# ProPrj_C64_Printer_Interface_2025-09-17.net
KiCad netlist of a schematic drawn in EasyEDA Pro
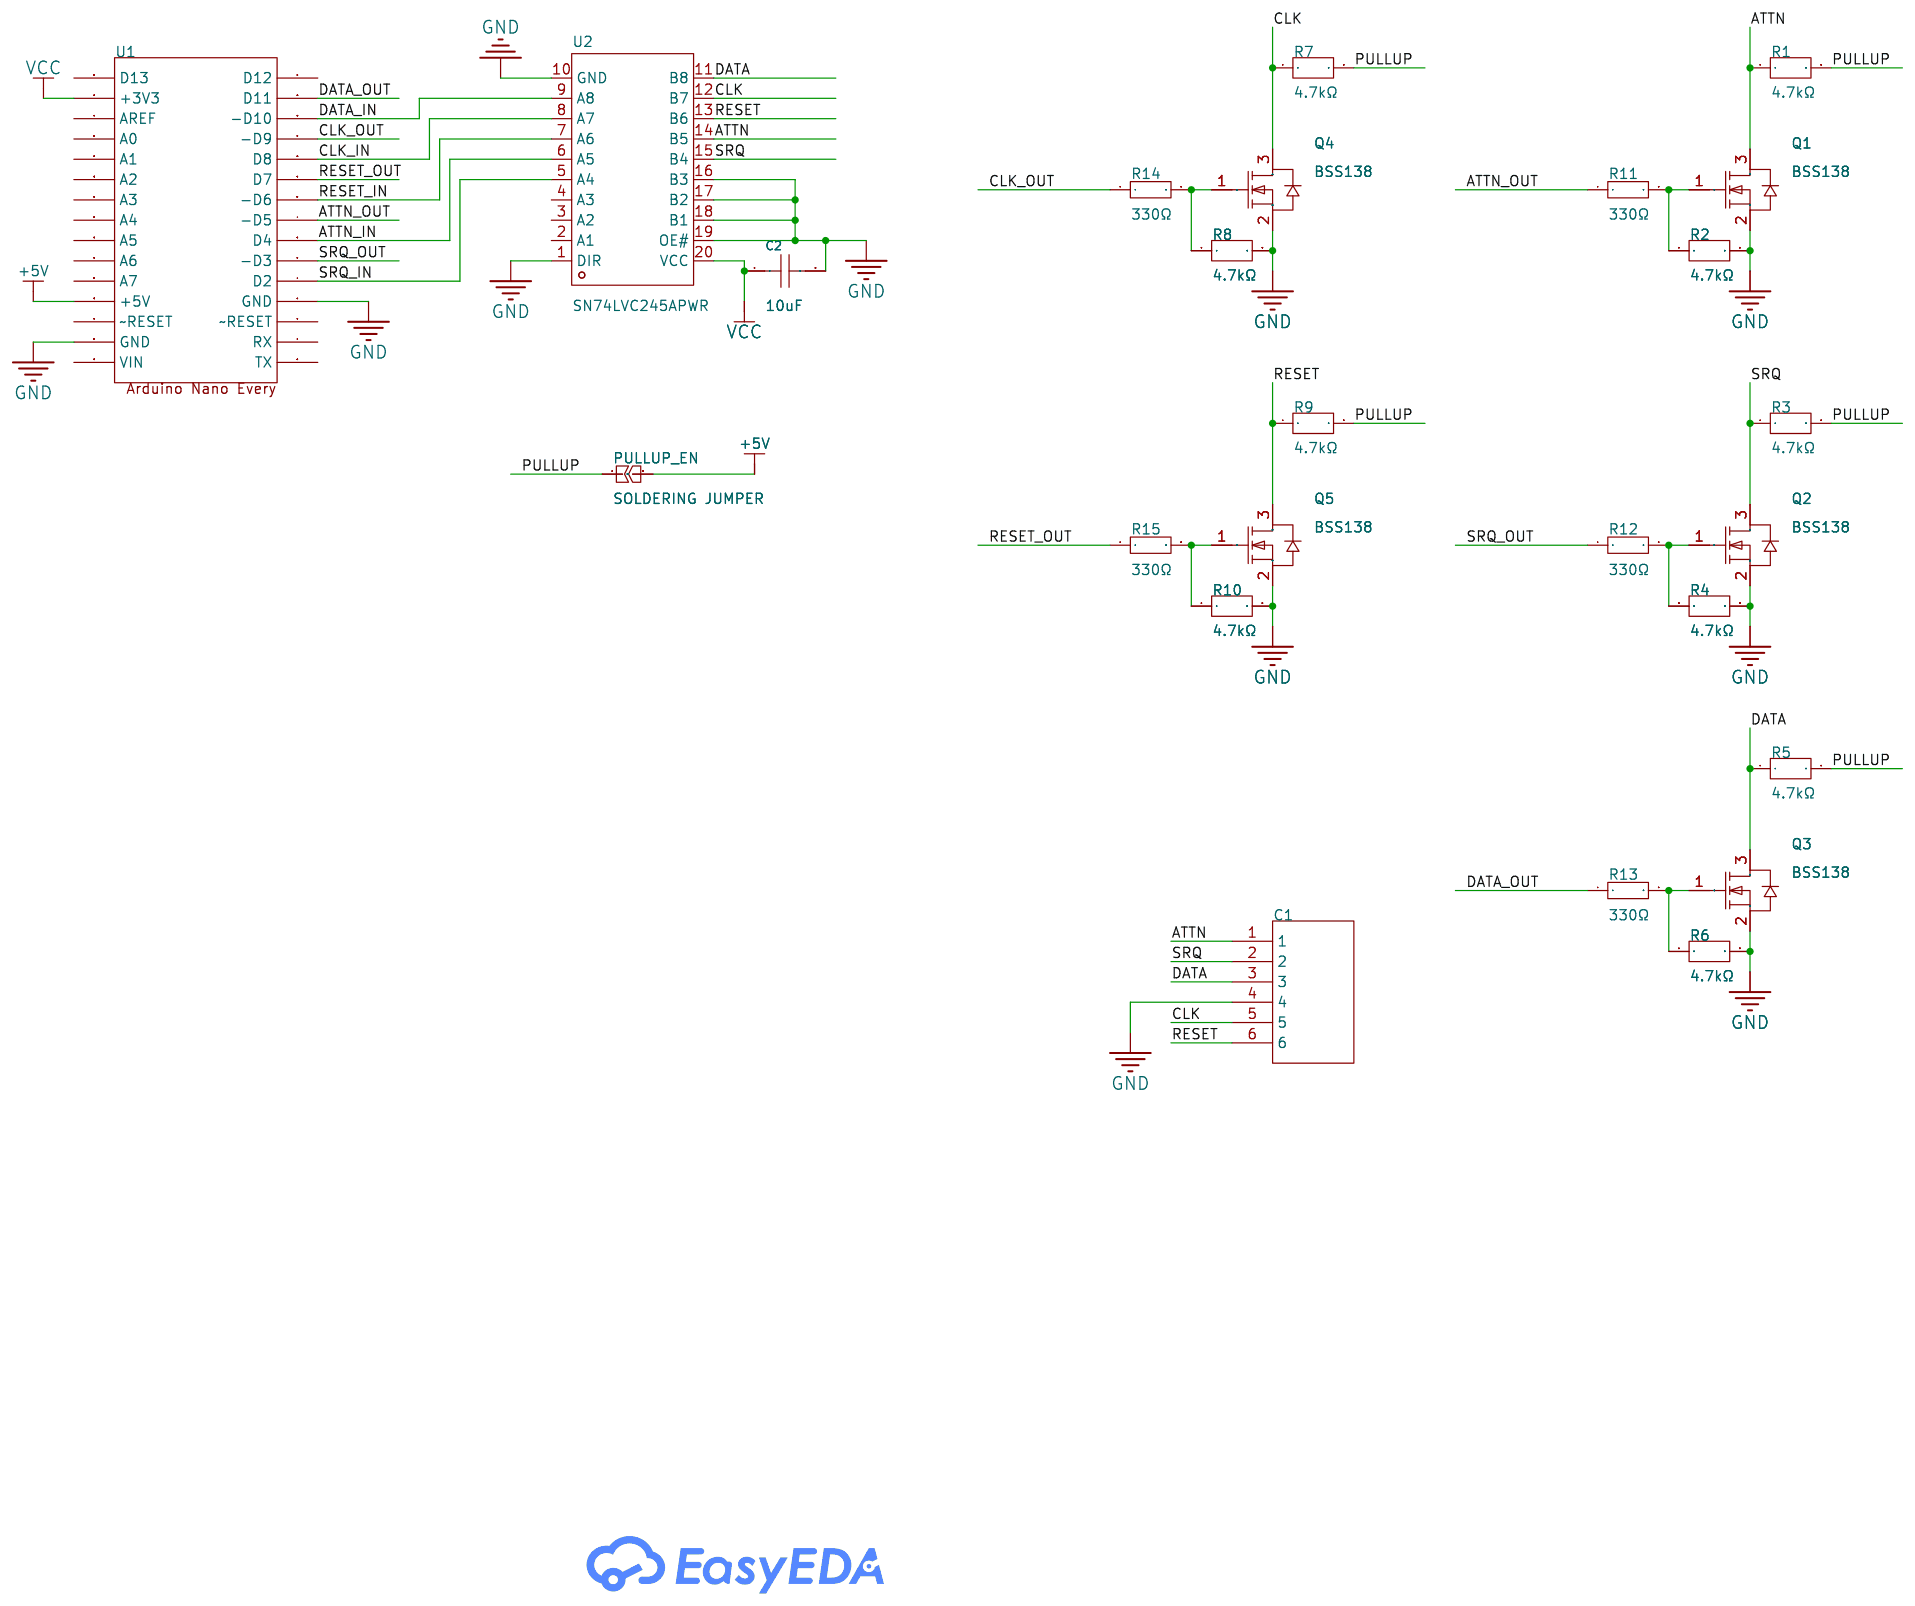
[diagram p0: schematic sheet]

(export (version "E")
  (design (tool "Eeschema 10.0.6"))
  (components
    (comp (ref "C1")
      (value "DIN 6")
      (footprint "easyedapro:FC680806")
      (libsource (lib "easyedapro") (part "FC680806 DIN 6 240°"))
    )
    (comp (ref "C2")
      (value "10uF")
      (footprint "easyedapro:C0603")
      (description "Capacitance:10uF Tolerance:±20% Tolerance:±20% Voltage Rating:25V Temperature Coefficient:X5R")
      (fields
        (field (name "Manufacturer Part") "CL10A106MA8NRNC")
        (field (name "Manufacturer") "SAMSUNG(三星)")
      )
      (libsource (lib "easyedapro") (part "CL10A106MA8NRNC"))
    )
    (comp (ref "PULLUP_EN")
      (value "SOLDERING JUMPER")
      (footprint "easyedapro:JUMPER")
      (libsource (lib "easyedapro") (part "Jumper 3pin"))
    )
    (comp (ref "Q1")
      (value "BSS138")
      (footprint "easyedapro:SOT-23_L2.9-W1.3-P1.90-LS2.4-BR")
      (fields (field (name "Manufacturer") "GOODWORK(固得沃克)"))
      (libsource (lib "easyedapro") (part "BSS138_C2938375"))
    )
    (comp (ref "Q2")
      (value "BSS138")
      (footprint "easyedapro:SOT-23_L2.9-W1.3-P1.90-LS2.4-BR")
      (fields (field (name "Manufacturer") "GOODWORK(固得沃克)"))
      (libsource (lib "easyedapro") (part "BSS138_C2938375"))
    )
    (comp (ref "Q3")
      (value "BSS138")
      (footprint "easyedapro:SOT-23_L2.9-W1.3-P1.90-LS2.4-BR")
      (fields (field (name "Manufacturer") "GOODWORK(固得沃克)"))
      (libsource (lib "easyedapro") (part "BSS138_C2938375"))
    )
    (comp (ref "Q4")
      (value "BSS138")
      (footprint "easyedapro:SOT-23_L2.9-W1.3-P1.90-LS2.4-BR")
      (fields (field (name "Manufacturer") "GOODWORK(固得沃克)"))
      (libsource (lib "easyedapro") (part "BSS138_C2938375"))
    )
    (comp (ref "Q5")
      (value "BSS138")
      (footprint "easyedapro:SOT-23_L2.9-W1.3-P1.90-LS2.4-BR")
      (fields (field (name "Manufacturer") "GOODWORK(固得沃克)"))
      (libsource (lib "easyedapro") (part "BSS138_C2938375"))
    )
    (comp (ref "R1")
      (value "4.7kΩ")
      (footprint "easyedapro:R0805")
      (fields (field (name "Manufacturer Part") "ERJ6RBD4701V") (field (name "Manufacturer") "PANASONIC(松下)"))
      (libsource (lib "easyedapro") (part "ERJ6RBD4701V"))
    )
    (comp (ref "R2")
      (value "4.7kΩ")
      (footprint "easyedapro:R0805")
      (fields (field (name "Manufacturer Part") "ERJ6RBD4701V") (field (name "Manufacturer") "PANASONIC(松下)"))
      (libsource (lib "easyedapro") (part "ERJ6RBD4701V"))
    )
    (comp (ref "R3")
      (value "4.7kΩ")
      (footprint "easyedapro:R0805")
      (fields (field (name "Manufacturer Part") "ERJ6RBD4701V") (field (name "Manufacturer") "PANASONIC(松下)"))
      (libsource (lib "easyedapro") (part "ERJ6RBD4701V"))
    )
    (comp (ref "R4")
      (value "4.7kΩ")
      (footprint "easyedapro:R0805")
      (fields (field (name "Manufacturer Part") "ERJ6RBD4701V") (field (name "Manufacturer") "PANASONIC(松下)"))
      (libsource (lib "easyedapro") (part "ERJ6RBD4701V"))
    )
    (comp (ref "R5")
      (value "4.7kΩ")
      (footprint "easyedapro:R0805")
      (fields (field (name "Manufacturer Part") "ERJ6RBD4701V") (field (name "Manufacturer") "PANASONIC(松下)"))
      (libsource (lib "easyedapro") (part "ERJ6RBD4701V"))
    )
    (comp (ref "R6")
      (value "4.7kΩ")
      (footprint "easyedapro:R0805")
      (fields (field (name "Manufacturer Part") "ERJ6RBD4701V") (field (name "Manufacturer") "PANASONIC(松下)"))
      (libsource (lib "easyedapro") (part "ERJ6RBD4701V"))
    )
    (comp (ref "R7")
      (value "4.7kΩ")
      (footprint "easyedapro:R0805")
      (fields (field (name "Manufacturer Part") "ERJ6RBD4701V") (field (name "Manufacturer") "PANASONIC(松下)"))
      (libsource (lib "easyedapro") (part "ERJ6RBD4701V"))
    )
    (comp (ref "R8")
      (value "4.7kΩ")
      (footprint "easyedapro:R0805")
      (fields (field (name "Manufacturer Part") "ERJ6RBD4701V") (field (name "Manufacturer") "PANASONIC(松下)"))
      (libsource (lib "easyedapro") (part "ERJ6RBD4701V"))
    )
    (comp (ref "R9")
      (value "4.7kΩ")
      (footprint "easyedapro:R0805")
      (fields (field (name "Manufacturer Part") "ERJ6RBD4701V") (field (name "Manufacturer") "PANASONIC(松下)"))
      (libsource (lib "easyedapro") (part "ERJ6RBD4701V"))
    )
    (comp (ref "R10")
      (value "4.7kΩ")
      (footprint "easyedapro:R0805")
      (fields (field (name "Manufacturer Part") "ERJ6RBD4701V") (field (name "Manufacturer") "PANASONIC(松下)"))
      (libsource (lib "easyedapro") (part "ERJ6RBD4701V"))
    )
    (comp (ref "R11")
      (value "330Ω")
      (footprint "easyedapro:R0603")
      (fields
        (field (name "Manufacturer Part") "0603WAF3300T5E")
        (field (name "Manufacturer") "UNI-ROYAL(厚声)")
      )
      (libsource (lib "easyedapro") (part "0603WAF3300T5E"))
    )
    (comp (ref "R12")
      (value "330Ω")
      (footprint "easyedapro:R0603")
      (fields
        (field (name "Manufacturer Part") "0603WAF3300T5E")
        (field (name "Manufacturer") "UNI-ROYAL(厚声)")
      )
      (libsource (lib "easyedapro") (part "0603WAF3300T5E"))
    )
    (comp (ref "R13")
      (value "330Ω")
      (footprint "easyedapro:R0603")
      (fields
        (field (name "Manufacturer Part") "0603WAF3300T5E")
        (field (name "Manufacturer") "UNI-ROYAL(厚声)")
      )
      (libsource (lib "easyedapro") (part "0603WAF3300T5E"))
    )
    (comp (ref "R14")
      (value "330Ω")
      (footprint "easyedapro:R0603")
      (fields
        (field (name "Manufacturer Part") "0603WAF3300T5E")
        (field (name "Manufacturer") "UNI-ROYAL(厚声)")
      )
      (libsource (lib "easyedapro") (part "0603WAF3300T5E"))
    )
    (comp (ref "R15")
      (value "330Ω")
      (footprint "easyedapro:R0603")
      (fields
        (field (name "Manufacturer Part") "0603WAF3300T5E")
        (field (name "Manufacturer") "UNI-ROYAL(厚声)")
      )
      (libsource (lib "easyedapro") (part "0603WAF3300T5E"))
    )
    (comp (ref "U1")
      (value "~")
      (footprint "easyedapro:Arduino Nano Every (SMD)")
      (libsource (lib "easyedapro") (part "Arduino Nano Every"))
    )
    (comp (ref "U2")
      (value "SN74LVC245APWR")
      (footprint "easyedapro:TSSOP-20_L6.5-W4.4-P0.65-LS6.4-BL")
      (fields (field (name "Manufacturer") "TI(德州仪器)"))
      (libsource (lib "easyedapro") (part "SN74LVC245APWR"))
    )
  )
  (nets
    (net (code "1") (name "+5V") (class "Default")
      (node (ref "PULLUP_EN") (pin "2") (pinfunction "2_2") (pintype "input"))
      (node (ref "U1") (pin "26") (pinfunction "+5V_26") (pintype "input"))
    )
    (net (code "2") (name "/ATTN") (class "Default")
      (node (ref "C1") (pin "1") (pinfunction "1_1") (pintype "input"))
      (node (ref "Q1") (pin "3") (pinfunction "D_3") (pintype "unspecified"))
      (node (ref "R1") (pin "1") (pinfunction "1_1") (pintype "unspecified"))
      (node (ref "U2") (pin "14") (pinfunction "B5_14") (pintype "unspecified"))
    )
    (net (code "3") (name "/ATTN_IN") (class "Default")
      (node (ref "U1") (pin "6") (pinfunction "D4_6") (pintype "input"))
      (node (ref "U2") (pin "6") (pinfunction "A5_6") (pintype "unspecified"))
    )
    (net (code "4") (name "/ATTN_OUT") (class "Default")
      (node (ref "R11") (pin "1") (pinfunction "1_1") (pintype "input"))
      (node (ref "U1") (pin "7") (pinfunction "-D5_7") (pintype "input"))
    )
    (net (code "5") (name "/CLK") (class "Default")
      (node (ref "C1") (pin "5") (pinfunction "5_5") (pintype "input"))
      (node (ref "Q4") (pin "3") (pinfunction "D_3") (pintype "unspecified"))
      (node (ref "R7") (pin "1") (pinfunction "1_1") (pintype "unspecified"))
      (node (ref "U2") (pin "12") (pinfunction "B7_12") (pintype "unspecified"))
    )
    (net (code "6") (name "/CLK_IN") (class "Default")
      (node (ref "U1") (pin "10") (pinfunction "D8_10") (pintype "input"))
      (node (ref "U2") (pin "8") (pinfunction "A7_8") (pintype "unspecified"))
    )
    (net (code "7") (name "/CLK_OUT") (class "Default")
      (node (ref "R14") (pin "1") (pinfunction "1_1") (pintype "input"))
      (node (ref "U1") (pin "11") (pinfunction "-D9_11") (pintype "input"))
    )
    (net (code "8") (name "/DATA") (class "Default")
      (node (ref "C1") (pin "3") (pinfunction "3_3") (pintype "input"))
      (node (ref "Q3") (pin "3") (pinfunction "D_3") (pintype "unspecified"))
      (node (ref "R5") (pin "1") (pinfunction "1_1") (pintype "unspecified"))
      (node (ref "U2") (pin "11") (pinfunction "B8_11") (pintype "unspecified"))
    )
    (net (code "9") (name "/DATA_IN") (class "Default")
      (node (ref "U1") (pin "12") (pinfunction "-D10_12") (pintype "input"))
      (node (ref "U2") (pin "9") (pinfunction "A8_9") (pintype "unspecified"))
    )
    (net (code "10") (name "/DATA_OUT") (class "Default")
      (node (ref "R13") (pin "1") (pinfunction "1_1") (pintype "input"))
      (node (ref "U1") (pin "13") (pinfunction "D11_13") (pintype "input"))
    )
    (net (code "11") (name "/PULLUP") (class "Default")
      (node (ref "PULLUP_EN") (pin "1") (pinfunction "1_1") (pintype "input"))
      (node (ref "R1") (pin "2") (pinfunction "2_2") (pintype "unspecified"))
      (node (ref "R3") (pin "2") (pinfunction "2_2") (pintype "unspecified"))
      (node (ref "R5") (pin "2") (pinfunction "2_2") (pintype "unspecified"))
      (node (ref "R7") (pin "2") (pinfunction "2_2") (pintype "unspecified"))
      (node (ref "R9") (pin "2") (pinfunction "2_2") (pintype "unspecified"))
    )
    (net (code "12") (name "/RESET") (class "Default")
      (node (ref "C1") (pin "6") (pinfunction "6_6") (pintype "input"))
      (node (ref "Q5") (pin "3") (pinfunction "D_3") (pintype "unspecified"))
      (node (ref "R9") (pin "1") (pinfunction "1_1") (pintype "unspecified"))
      (node (ref "U2") (pin "13") (pinfunction "B6_13") (pintype "unspecified"))
    )
    (net (code "13") (name "/RESET_IN") (class "Default")
      (node (ref "U1") (pin "8") (pinfunction "-D6_8") (pintype "input"))
      (node (ref "U2") (pin "7") (pinfunction "A6_7") (pintype "unspecified"))
    )
    (net (code "14") (name "/RESET_OUT") (class "Default")
      (node (ref "R15") (pin "1") (pinfunction "1_1") (pintype "input"))
      (node (ref "U1") (pin "9") (pinfunction "D7_9") (pintype "input"))
    )
    (net (code "15") (name "/SRQ") (class "Default")
      (node (ref "C1") (pin "2") (pinfunction "2_2") (pintype "input"))
      (node (ref "Q2") (pin "3") (pinfunction "D_3") (pintype "unspecified"))
      (node (ref "R3") (pin "1") (pinfunction "1_1") (pintype "unspecified"))
      (node (ref "U2") (pin "15") (pinfunction "B4_15") (pintype "unspecified"))
    )
    (net (code "16") (name "/SRQ_IN") (class "Default")
      (node (ref "U1") (pin "4") (pinfunction "D2_4") (pintype "input"))
      (node (ref "U2") (pin "5") (pinfunction "A4_5") (pintype "unspecified"))
    )
    (net (code "17") (name "/SRQ_OUT") (class "Default")
      (node (ref "R12") (pin "1") (pinfunction "1_1") (pintype "input"))
      (node (ref "U1") (pin "5") (pinfunction "-D3_5") (pintype "input"))
    )
    (net (code "18") (name "GND") (class "Default")
      (node (ref "C1") (pin "4") (pinfunction "4_4") (pintype "input"))
      (node (ref "C2") (pin "2") (pinfunction "2_2") (pintype "input"))
      (node (ref "Q1") (pin "2") (pinfunction "S_2") (pintype "unspecified"))
      (node (ref "Q2") (pin "2") (pinfunction "S_2") (pintype "unspecified"))
      (node (ref "Q3") (pin "2") (pinfunction "S_2") (pintype "unspecified"))
      (node (ref "Q4") (pin "2") (pinfunction "S_2") (pintype "unspecified"))
      (node (ref "Q5") (pin "2") (pinfunction "S_2") (pintype "unspecified"))
      (node (ref "R10") (pin "2") (pinfunction "2_2") (pintype "unspecified"))
      (node (ref "R2") (pin "2") (pinfunction "2_2") (pintype "unspecified"))
      (node (ref "R4") (pin "2") (pinfunction "2_2") (pintype "unspecified"))
      (node (ref "R6") (pin "2") (pinfunction "2_2") (pintype "unspecified"))
      (node (ref "R8") (pin "2") (pinfunction "2_2") (pintype "unspecified"))
      (node (ref "U1") (pin "28") (pinfunction "GND_28") (pintype "input"))
      (node (ref "U1") (pin "3") (pinfunction "GND_3") (pintype "input"))
      (node (ref "U2") (pin "1") (pinfunction "DIR_1") (pintype "unspecified"))
      (node (ref "U2") (pin "10") (pinfunction "GND_10") (pintype "unspecified"))
      (node (ref "U2") (pin "16") (pinfunction "B3_16") (pintype "unspecified"))
      (node (ref "U2") (pin "17") (pinfunction "B2_17") (pintype "unspecified"))
      (node (ref "U2") (pin "18") (pinfunction "B1_18") (pintype "unspecified"))
      (node (ref "U2") (pin "19") (pinfunction "OE#_19") (pintype "unspecified"))
    )
    (net (code "19") (name "Net-(Q1-G)") (class "Default")
      (node (ref "Q1") (pin "1") (pinfunction "G_1") (pintype "unspecified"))
      (node (ref "R11") (pin "2") (pinfunction "2_2") (pintype "input"))
      (node (ref "R2") (pin "1") (pinfunction "1_1") (pintype "unspecified"))
    )
    (net (code "20") (name "Net-(Q2-G)") (class "Default")
      (node (ref "Q2") (pin "1") (pinfunction "G_1") (pintype "unspecified"))
      (node (ref "R12") (pin "2") (pinfunction "2_2") (pintype "input"))
      (node (ref "R4") (pin "1") (pinfunction "1_1") (pintype "unspecified"))
    )
    (net (code "21") (name "Net-(Q3-G)") (class "Default")
      (node (ref "Q3") (pin "1") (pinfunction "G_1") (pintype "unspecified"))
      (node (ref "R13") (pin "2") (pinfunction "2_2") (pintype "input"))
      (node (ref "R6") (pin "1") (pinfunction "1_1") (pintype "unspecified"))
    )
    (net (code "22") (name "Net-(Q4-G)") (class "Default")
      (node (ref "Q4") (pin "1") (pinfunction "G_1") (pintype "unspecified"))
      (node (ref "R14") (pin "2") (pinfunction "2_2") (pintype "input"))
      (node (ref "R8") (pin "1") (pinfunction "1_1") (pintype "unspecified"))
    )
    (net (code "23") (name "Net-(Q5-G)") (class "Default")
      (node (ref "Q5") (pin "1") (pinfunction "G_1") (pintype "unspecified"))
      (node (ref "R10") (pin "1") (pinfunction "1_1") (pintype "unspecified"))
      (node (ref "R15") (pin "2") (pinfunction "2_2") (pintype "input"))
    )
    (net (code "24") (name "VCC") (class "Default")
      (node (ref "C2") (pin "1") (pinfunction "1_1") (pintype "input"))
      (node (ref "U1") (pin "16") (pinfunction "+3V3_16") (pintype "input"))
      (node (ref "U2") (pin "20") (pinfunction "VCC_20") (pintype "unspecified"))
    )
    (net (code "25") (name "unconnected-(U1-A0-Pad18)") (class "Default")
      (node (ref "U1") (pin "18") (pinfunction "A0_18") (pintype "input"))
    )
    (net (code "26") (name "unconnected-(U1-A1-Pad19)") (class "Default")
      (node (ref "U1") (pin "19") (pinfunction "A1_19") (pintype "input"))
    )
    (net (code "27") (name "unconnected-(U1-A2-Pad20)") (class "Default")
      (node (ref "U1") (pin "20") (pinfunction "A2_20") (pintype "input"))
    )
    (net (code "28") (name "unconnected-(U1-A3-Pad21)") (class "Default")
      (node (ref "U1") (pin "21") (pinfunction "A3_21") (pintype "input"))
    )
    (net (code "29") (name "unconnected-(U1-A4-Pad22)") (class "Default")
      (node (ref "U1") (pin "22") (pinfunction "A4_22") (pintype "input"))
    )
    (net (code "30") (name "unconnected-(U1-A5-Pad23)") (class "Default")
      (node (ref "U1") (pin "23") (pinfunction "A5_23") (pintype "input"))
    )
    (net (code "31") (name "unconnected-(U1-A6-Pad24)") (class "Default")
      (node (ref "U1") (pin "24") (pinfunction "A6_24") (pintype "input"))
    )
    (net (code "32") (name "unconnected-(U1-A7-Pad25)") (class "Default")
      (node (ref "U1") (pin "25") (pinfunction "A7_25") (pintype "input"))
    )
    (net (code "33") (name "unconnected-(U1-AREF-Pad17)") (class "Default")
      (node (ref "U1") (pin "17") (pinfunction "AREF_17") (pintype "input"))
    )
    (net (code "34") (name "unconnected-(U1-D12-Pad14)") (class "Default")
      (node (ref "U1") (pin "14") (pinfunction "D12_14") (pintype "input"))
    )
    (net (code "35") (name "unconnected-(U1-D13-Pad15)") (class "Default")
      (node (ref "U1") (pin "15") (pinfunction "D13_15") (pintype "input"))
    )
    (net (code "36") (name "unconnected-(U1-RX-Pad1)") (class "Default")
      (node (ref "U1") (pin "1") (pinfunction "RX_1") (pintype "input"))
    )
    (net (code "37") (name "unconnected-(U1-TX-Pad0)") (class "Default")
      (node (ref "U1") (pin "0") (pinfunction "TX_0") (pintype "input"))
    )
    (net (code "38") (name "unconnected-(U1-VIN-Pad29)") (class "Default")
      (node (ref "U1") (pin "29") (pinfunction "VIN_29") (pintype "input"))
    )
    (net (code "39") (name "unconnected-(U1-~RESET-Pad2)") (class "Default")
      (node (ref "U1") (pin "2") (pinfunction "~RESET_2") (pintype "input"))
    )
    (net (code "40") (name "unconnected-(U1-~RESET-Pad27)") (class "Default")
      (node (ref "U1") (pin "27") (pinfunction "~RESET_27") (pintype "input"))
    )
    (net (code "41") (name "unconnected-(U2-A1-Pad2)") (class "Default")
      (node (ref "U2") (pin "2") (pinfunction "A1_2") (pintype "unspecified"))
    )
    (net (code "42") (name "unconnected-(U2-A2-Pad3)") (class "Default")
      (node (ref "U2") (pin "3") (pinfunction "A2_3") (pintype "unspecified"))
    )
    (net (code "43") (name "unconnected-(U2-A3-Pad4)") (class "Default")
      (node (ref "U2") (pin "4") (pinfunction "A3_4") (pintype "unspecified"))
    )
  )
)
